# io-board-a-6.net
KiCad netlist of a schematic drawn in EAGLE
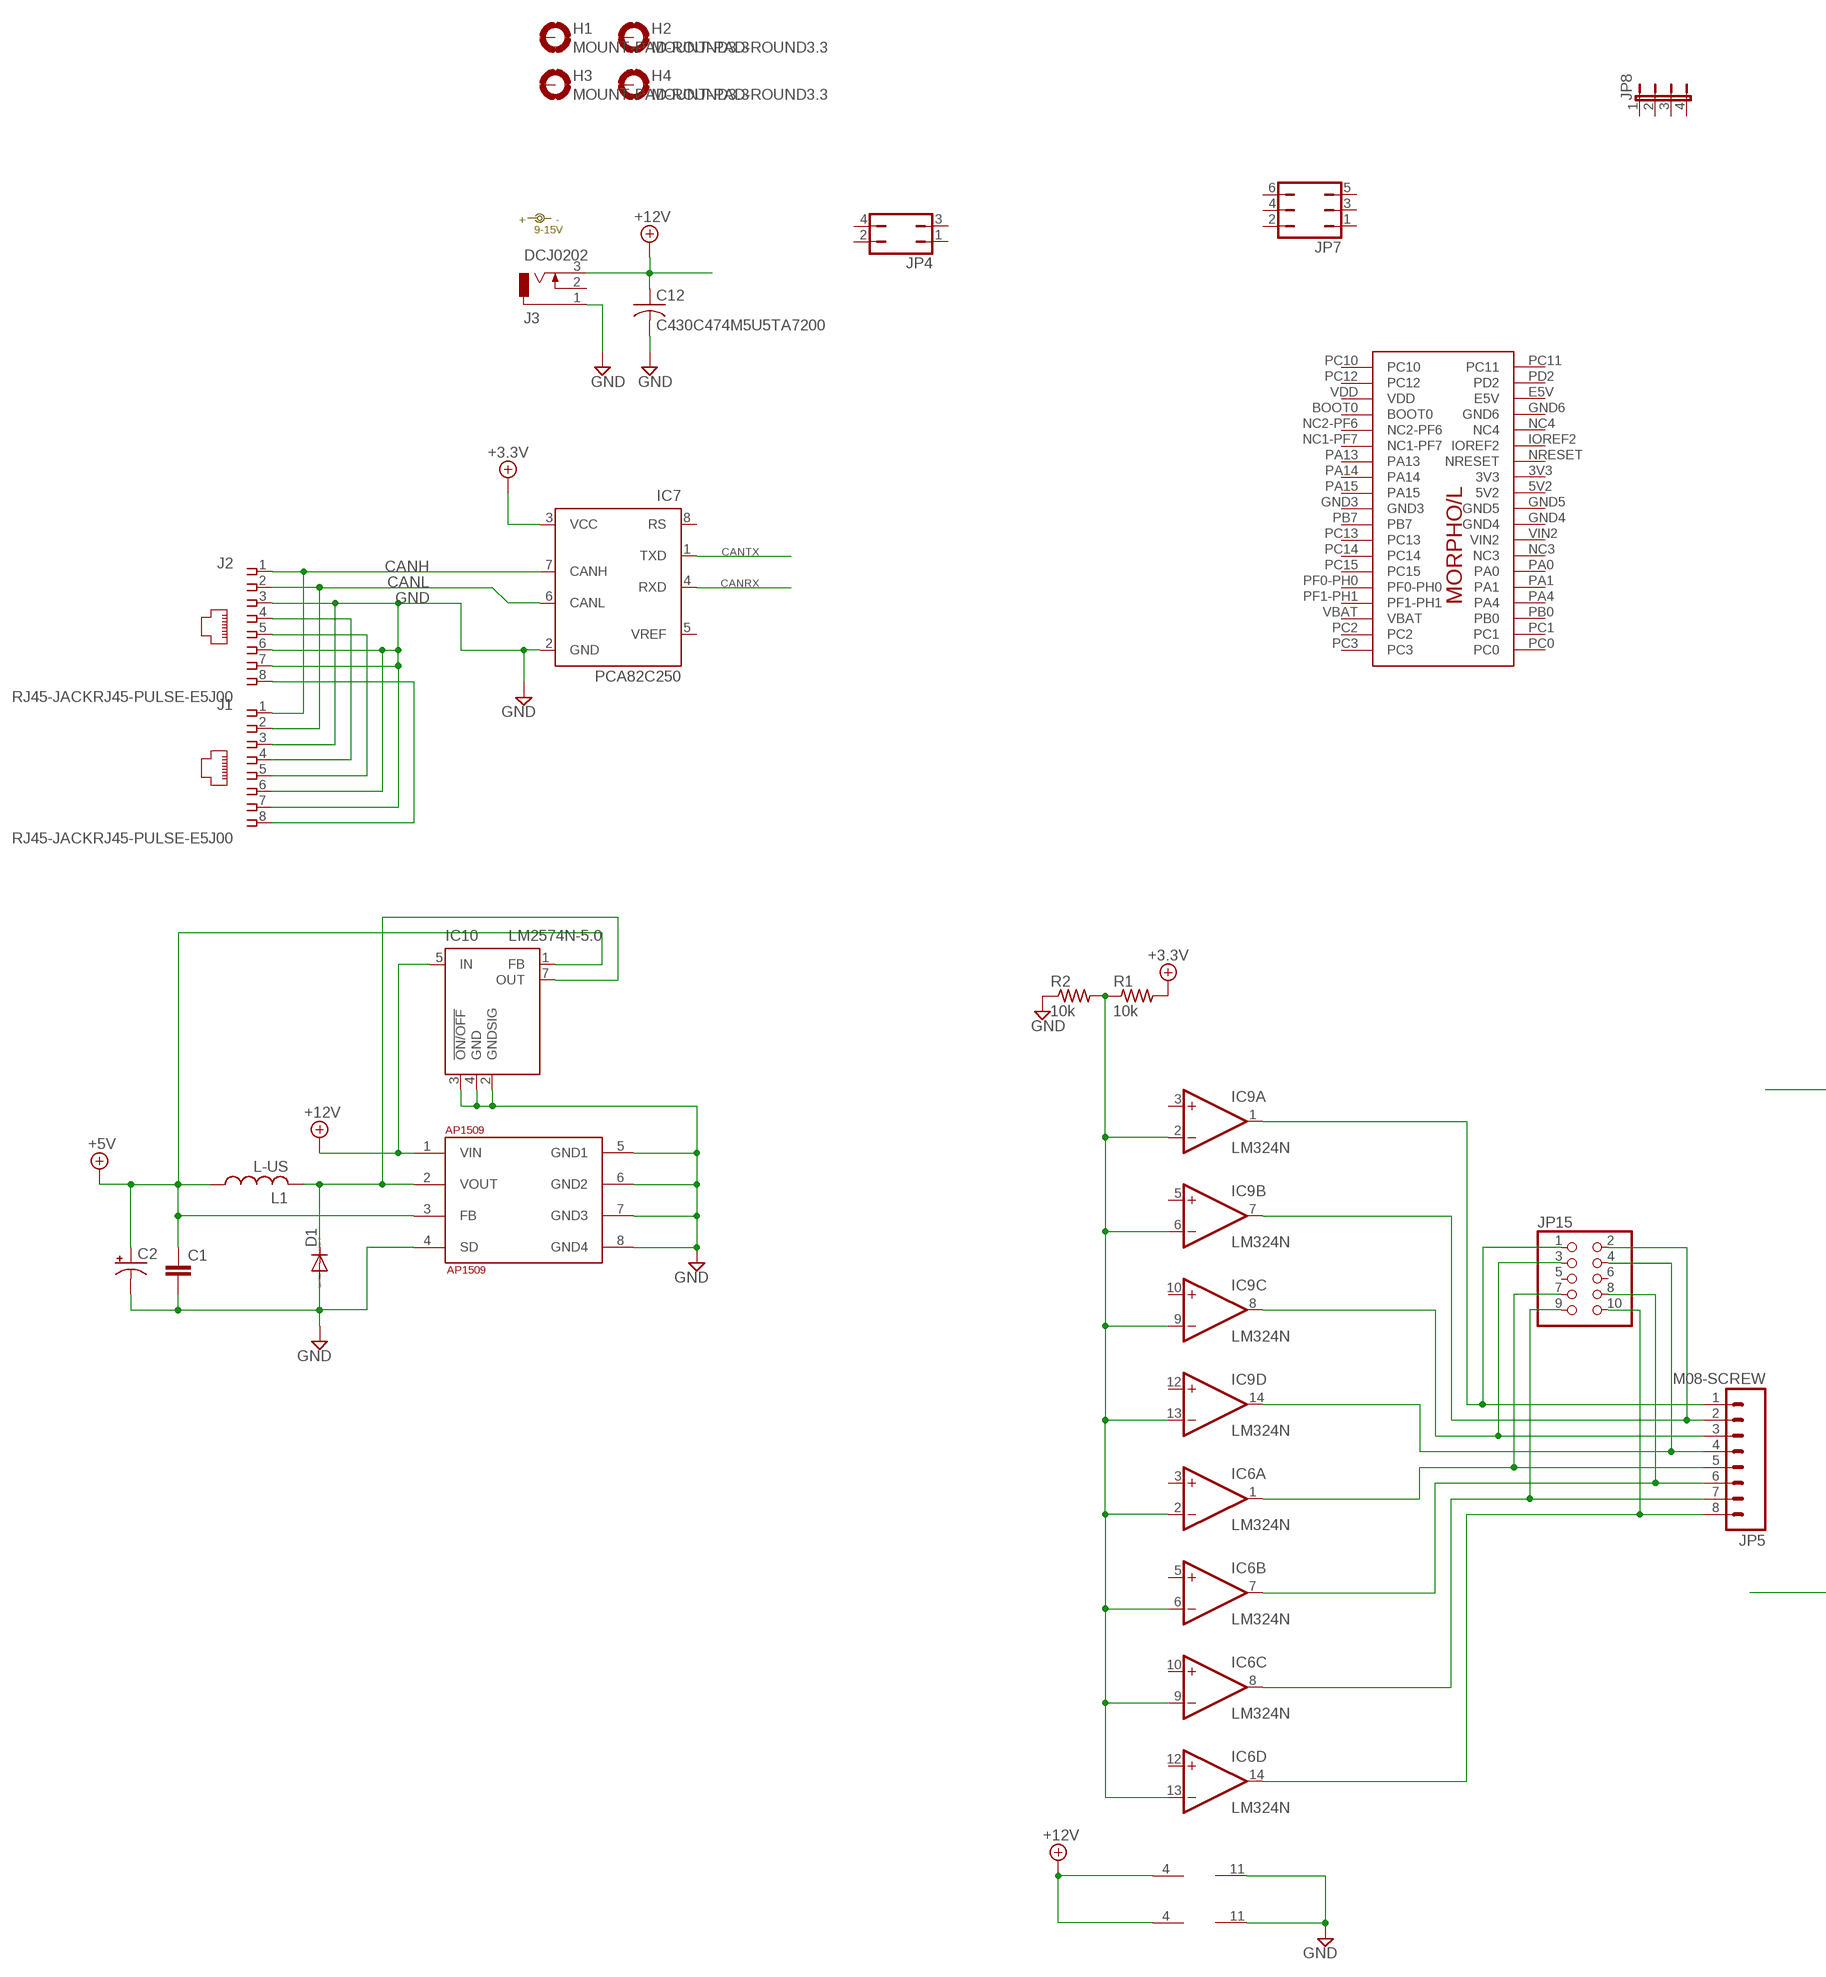
[diagram p0: schematic, sheet 1, part 1 of 2]
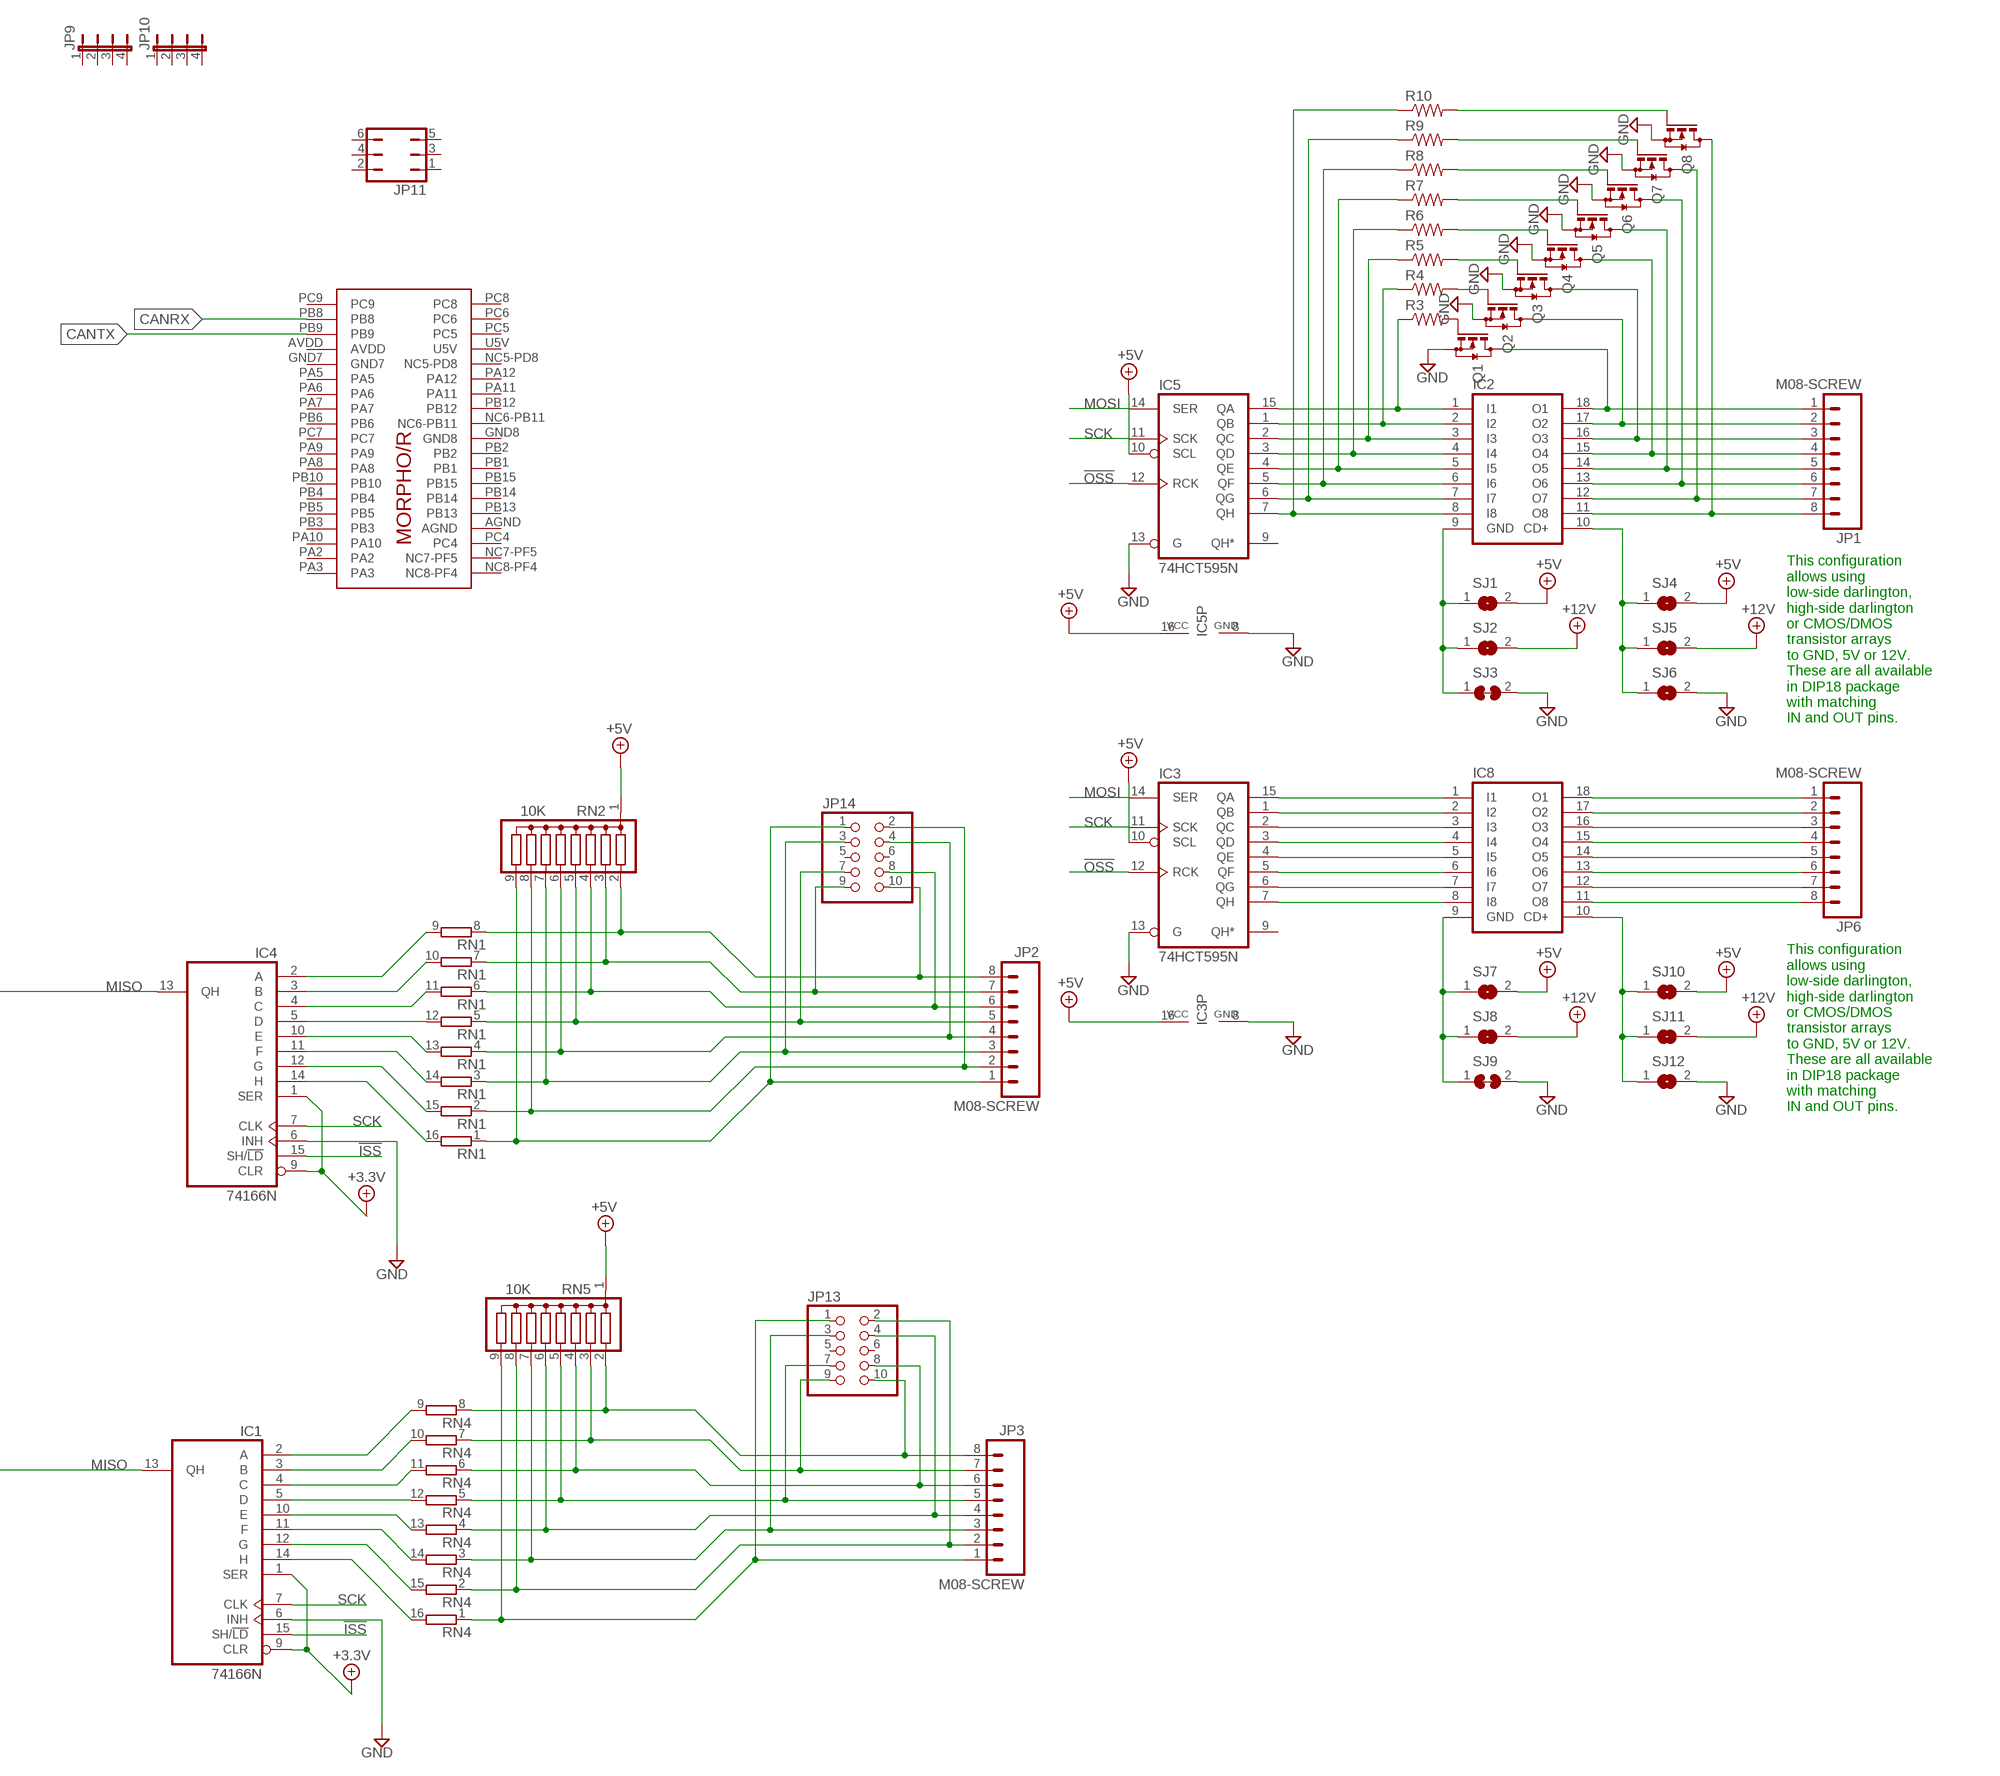
[diagram p1: schematic, sheet 1, part 2 of 2]

(export (version "E")
  (design (tool "Eeschema 10.0.6"))
  (components
    (comp (ref "+12V")
      (value "9-15V")
      (footprint "eagle-import:POWER_USAGE")
      (libsource (lib "eagle-import") (part "DOC-POWER_LABEL"))
    )
    (comp (ref "AP1509")
      (value "AP1509")
      (footprint "eagle-import:SO-08")
      (libsource (lib "eagle-import") (part "AP1509"))
    )
    (comp (ref "C1")
      (value "C-EUC1206")
      (footprint "eagle-import:C1206")
      (libsource (lib "eagle-import") (part "C-EUC1206"))
    )
    (comp (ref "C2")
      (value "CPOL-USE2.5-5")
      (footprint "eagle-import:E2,5-5")
      (libsource (lib "eagle-import") (part "CPOL-USE2.5-5"))
    )
    (comp (ref "C12")
      (value "C430C474M5U5TA7200")
      (footprint "eagle-import:C075-032X103")
      (libsource (lib "eagle-import") (part "C-US075-032X103"))
    )
    (comp (ref "D1")
      (value "DIODE-DO41-7.6")
      (footprint "eagle-import:DO41-7.6")
      (libsource (lib "eagle-import") (part "DIODE-DO41-7.6"))
    )
    (comp (ref "H1")
      (value "MOUNT-PAD-ROUND3.3")
      (footprint "eagle-import:3,3-PAD")
      (libsource (lib "eagle-import") (part "MOUNT-PAD-ROUND3.3"))
    )
    (comp (ref "H2")
      (value "MOUNT-PAD-ROUND3.3")
      (footprint "eagle-import:3,3-PAD")
      (libsource (lib "eagle-import") (part "MOUNT-PAD-ROUND3.3"))
    )
    (comp (ref "H3")
      (value "MOUNT-PAD-ROUND3.3")
      (footprint "eagle-import:3,3-PAD")
      (libsource (lib "eagle-import") (part "MOUNT-PAD-ROUND3.3"))
    )
    (comp (ref "H4")
      (value "MOUNT-PAD-ROUND3.3")
      (footprint "eagle-import:3,3-PAD")
      (libsource (lib "eagle-import") (part "MOUNT-PAD-ROUND3.3"))
    )
    (comp (ref "IC1")
      (value "74166N")
      (footprint "eagle-import:DIL16")
      (libsource (lib "eagle-import") (part "74166N"))
    )
    (comp (ref "IC2")
      (value "ULN2803A")
      (footprint "eagle-import:DIL18-THIN")
      (libsource (lib "eagle-import") (part "ULN2803A"))
    )
    (comp (ref "IC3")
      (value "74HCT595N")
      (footprint "eagle-import:DIL16")
      (libsource (lib "eagle-import") (part "74595NHCT"))
    )
    (comp (ref "IC4")
      (value "74166N")
      (footprint "eagle-import:DIL16")
      (libsource (lib "eagle-import") (part "74166N"))
    )
    (comp (ref "IC5")
      (value "74HCT595N")
      (footprint "eagle-import:DIL16")
      (libsource (lib "eagle-import") (part "74595NHCT"))
    )
    (comp (ref "IC6")
      (value "LM324N")
      (footprint "eagle-import:DIL14")
      (libsource (lib "eagle-import") (part "LM324N"))
    )
    (comp (ref "IC7")
      (value "PCA82C250")
      (footprint "eagle-import:DIL08")
      (libsource (lib "eagle-import") (part "PCA82C250"))
    )
    (comp (ref "IC8")
      (value "ULN2803A")
      (footprint "eagle-import:DIL18-THIN")
      (libsource (lib "eagle-import") (part "ULN2803A"))
    )
    (comp (ref "IC9")
      (value "LM324N")
      (footprint "eagle-import:DIL14")
      (libsource (lib "eagle-import") (part "LM324N"))
    )
    (comp (ref "IC10")
      (value "LM2574N-5.0")
      (footprint "eagle-import:DIL08")
      (libsource (lib "eagle-import") (part "LM2574?-N5.0"))
    )
    (comp (ref "J1")
      (value "RJ45-JACKRJ45-PULSE-E5J00")
      (footprint "eagle-import:RJ45-PULSE-E5J88")
      (libsource (lib "eagle-import") (part "RJ45-JACKRJ45-PULSE-E5J00"))
    )
    (comp (ref "J2")
      (value "RJ45-JACKRJ45-PULSE-E5J00")
      (footprint "eagle-import:RJ45-PULSE-E5J88")
      (libsource (lib "eagle-import") (part "RJ45-JACKRJ45-PULSE-E5J00"))
    )
    (comp (ref "J3")
      (value "DCJ0202")
      (footprint "eagle-import:DCJ0202")
      (libsource (lib "eagle-import") (part "DCJ0202"))
    )
    (comp (ref "JP1")
      (value "M08-SCREW")
      (footprint "eagle-import:1X08_TERMINAL")
      (libsource (lib "eagle-import") (part "M08-SCREW"))
    )
    (comp (ref "JP2")
      (value "M08-SCREW")
      (footprint "eagle-import:1X08_TERMINAL")
      (libsource (lib "eagle-import") (part "M08-SCREW"))
    )
    (comp (ref "JP3")
      (value "M08-SCREW")
      (footprint "eagle-import:1X08_TERMINAL")
      (libsource (lib "eagle-import") (part "M08-SCREW"))
    )
    (comp (ref "JP4")
      (value "JP2Q")
      (footprint "eagle-import:JP2Q")
      (libsource (lib "eagle-import") (part "JP2Q"))
    )
    (comp (ref "JP5")
      (value "M08-SCREW")
      (footprint "eagle-import:1X08_TERMINAL")
      (libsource (lib "eagle-import") (part "M08-SCREW"))
    )
    (comp (ref "JP6")
      (value "M08-SCREW")
      (footprint "eagle-import:1X08_TERMINAL")
      (libsource (lib "eagle-import") (part "M08-SCREW"))
    )
    (comp (ref "JP7")
      (value "JP3Q")
      (footprint "eagle-import:JP3Q")
      (libsource (lib "eagle-import") (part "JP3Q"))
    )
    (comp (ref "JP8")
      (value "JP4-FLAT")
      (footprint "eagle-import:JP4F")
      (libsource (lib "eagle-import") (part "JP4-FLAT"))
    )
    (comp (ref "JP9")
      (value "JP4-FLAT")
      (footprint "eagle-import:JP4F")
      (libsource (lib "eagle-import") (part "JP4-FLAT"))
    )
    (comp (ref "JP10")
      (value "JP4-FLAT")
      (footprint "eagle-import:JP4F")
      (libsource (lib "eagle-import") (part "JP4-FLAT"))
    )
    (comp (ref "JP11")
      (value "JP3Q")
      (footprint "eagle-import:JP3Q")
      (libsource (lib "eagle-import") (part "JP3Q"))
    )
    (comp (ref "JP13")
      (value "PINHD-2X5CN")
      (footprint "eagle-import:CON10M")
      (libsource (lib "eagle-import") (part "PINHD-2X5CN"))
    )
    (comp (ref "JP14")
      (value "PINHD-2X5CN")
      (footprint "eagle-import:CON10M")
      (libsource (lib "eagle-import") (part "PINHD-2X5CN"))
    )
    (comp (ref "JP15")
      (value "PINHD-2X5CN")
      (footprint "eagle-import:CON10M")
      (libsource (lib "eagle-import") (part "PINHD-2X5CN"))
    )
    (comp (ref "L1")
      (value "L-US")
      (footprint "eagle-import:L5-8,5")
      (libsource (lib "eagle-import") (part "L-US"))
    )
    (comp (ref "Q1")
      (value "BSS123")
      (footprint "eagle-import:SOT23")
      (libsource (lib "eagle-import") (part "BSS123"))
    )
    (comp (ref "Q2")
      (value "BSS123")
      (footprint "eagle-import:SOT23")
      (libsource (lib "eagle-import") (part "BSS123"))
    )
    (comp (ref "Q3")
      (value "BSS123")
      (footprint "eagle-import:SOT23")
      (libsource (lib "eagle-import") (part "BSS123"))
    )
    (comp (ref "Q4")
      (value "BSS123")
      (footprint "eagle-import:SOT23")
      (libsource (lib "eagle-import") (part "BSS123"))
    )
    (comp (ref "Q5")
      (value "BSS123")
      (footprint "eagle-import:SOT23")
      (libsource (lib "eagle-import") (part "BSS123"))
    )
    (comp (ref "Q6")
      (value "BSS123")
      (footprint "eagle-import:SOT23")
      (libsource (lib "eagle-import") (part "BSS123"))
    )
    (comp (ref "Q7")
      (value "BSS123")
      (footprint "eagle-import:SOT23")
      (libsource (lib "eagle-import") (part "BSS123"))
    )
    (comp (ref "Q8")
      (value "BSS123")
      (footprint "eagle-import:SOT23")
      (libsource (lib "eagle-import") (part "BSS123"))
    )
    (comp (ref "R1")
      (value "10k")
      (footprint "eagle-import:R1206")
      (libsource (lib "eagle-import") (part "R-US_R1206"))
    )
    (comp (ref "R2")
      (value "10k")
      (footprint "eagle-import:R1206")
      (libsource (lib "eagle-import") (part "R-US_R1206"))
    )
    (comp (ref "R3")
      (value "R-US_R0603")
      (footprint "eagle-import:R0603")
      (libsource (lib "eagle-import") (part "R-US_R0603"))
    )
    (comp (ref "R4")
      (value "R-US_R0603")
      (footprint "eagle-import:R0603")
      (libsource (lib "eagle-import") (part "R-US_R0603"))
    )
    (comp (ref "R5")
      (value "R-US_R0603")
      (footprint "eagle-import:R0603")
      (libsource (lib "eagle-import") (part "R-US_R0603"))
    )
    (comp (ref "R6")
      (value "R-US_R0603")
      (footprint "eagle-import:R0603")
      (libsource (lib "eagle-import") (part "R-US_R0603"))
    )
    (comp (ref "R7")
      (value "R-US_R0603")
      (footprint "eagle-import:R0603")
      (libsource (lib "eagle-import") (part "R-US_R0603"))
    )
    (comp (ref "R8")
      (value "R-US_R0603")
      (footprint "eagle-import:R0603")
      (libsource (lib "eagle-import") (part "R-US_R0603"))
    )
    (comp (ref "R9")
      (value "R-US_R0603")
      (footprint "eagle-import:R0603")
      (libsource (lib "eagle-import") (part "R-US_R0603"))
    )
    (comp (ref "R10")
      (value "R-US_R0603")
      (footprint "eagle-import:R0603")
      (libsource (lib "eagle-import") (part "R-US_R0603"))
    )
    (comp (ref "RN1")
      (value "8R-P")
      (footprint "eagle-import:DIL16")
      (libsource (lib "eagle-import") (part "8R-P"))
    )
    (comp (ref "RN2")
      (value "10K")
      (footprint "eagle-import:SIL9")
      (libsource (lib "eagle-import") (part "G08R"))
    )
    (comp (ref "RN4")
      (value "8R-P")
      (footprint "eagle-import:DIL16")
      (libsource (lib "eagle-import") (part "8R-P"))
    )
    (comp (ref "RN5")
      (value "10K")
      (footprint "eagle-import:SIL9")
      (libsource (lib "eagle-import") (part "G08R"))
    )
    (comp (ref "SJ1")
      (value "SJ")
      (footprint "eagle-import:SJ-RND")
      (libsource (lib "eagle-import") (part "SJ"))
    )
    (comp (ref "SJ2")
      (value "SJ")
      (footprint "eagle-import:SJ-RND")
      (libsource (lib "eagle-import") (part "SJ"))
    )
    (comp (ref "SJ3")
      (value "SJ-C")
      (footprint "eagle-import:SJW-C")
      (libsource (lib "eagle-import") (part "SJ-C"))
    )
    (comp (ref "SJ4")
      (value "SJ")
      (footprint "eagle-import:SJ-RND")
      (libsource (lib "eagle-import") (part "SJ"))
    )
    (comp (ref "SJ5")
      (value "SJ")
      (footprint "eagle-import:SJ-RND")
      (libsource (lib "eagle-import") (part "SJ"))
    )
    (comp (ref "SJ6")
      (value "SJ")
      (footprint "eagle-import:SJ-RND")
      (libsource (lib "eagle-import") (part "SJ"))
    )
    (comp (ref "SJ7")
      (value "SJ")
      (footprint "eagle-import:SJ-RND")
      (libsource (lib "eagle-import") (part "SJ"))
    )
    (comp (ref "SJ8")
      (value "SJ")
      (footprint "eagle-import:SJ-RND")
      (libsource (lib "eagle-import") (part "SJ"))
    )
    (comp (ref "SJ9")
      (value "SJ-C")
      (footprint "eagle-import:SJW-C")
      (libsource (lib "eagle-import") (part "SJ-C"))
    )
    (comp (ref "SJ10")
      (value "SJ")
      (footprint "eagle-import:SJ-RND")
      (libsource (lib "eagle-import") (part "SJ"))
    )
    (comp (ref "SJ11")
      (value "SJ")
      (footprint "eagle-import:SJ-RND")
      (libsource (lib "eagle-import") (part "SJ"))
    )
    (comp (ref "SJ12")
      (value "SJ")
      (footprint "eagle-import:SJ-RND")
      (libsource (lib "eagle-import") (part "SJ"))
    )
    (comp (ref "U$1")
      (value "NUCLEO_64_GENERIC")
      (footprint "eagle-import:NUCLEO_BRD_BASE64")
      (libsource (lib "eagle-import") (part "NUCLEO_64_GENERIC"))
    )
  )
  (nets
    (net (code "1") (name "+3.3V") (class "Default")
      (node (ref "IC1") (pin "1") (pinfunction "SER_1") (pintype "input"))
      (node (ref "IC1") (pin "9") (pinfunction "CLR_9") (pintype "input"))
      (node (ref "IC4") (pin "1") (pinfunction "SER_1") (pintype "input"))
      (node (ref "IC4") (pin "9") (pinfunction "CLR_9") (pintype "input"))
      (node (ref "IC7") (pin "3") (pinfunction "VCC_3") (pintype "power_in"))
      (node (ref "R1") (pin "2") (pinfunction "2_2") (pintype "passive"))
    )
    (net (code "2") (name "+5V") (class "Default")
      (node (ref "AP1509") (pin "3") (pinfunction "FB_3") (pintype "bidirectional"))
      (node (ref "C1") (pin "1") (pinfunction "1_1") (pintype "passive"))
      (node (ref "C2") (pin "+") (pinfunction "+_+") (pintype "passive"))
      (node (ref "IC10") (pin "1") (pinfunction "FB_1") (pintype "input"))
      (node (ref "IC3") (pin "10") (pinfunction "SCL_10") (pintype "input"))
      (node (ref "IC3") (pin "16") (pinfunction "VCC_16") (pintype "power_in"))
      (node (ref "IC5") (pin "10") (pinfunction "SCL_10") (pintype "input"))
      (node (ref "IC5") (pin "16") (pinfunction "VCC_16") (pintype "power_in"))
      (node (ref "L1") (pin "1") (pinfunction "1_1") (pintype "passive"))
      (node (ref "RN2") (pin "1") (pinfunction "1_1") (pintype "passive"))
      (node (ref "RN5") (pin "1") (pinfunction "1_1") (pintype "passive"))
      (node (ref "SJ1") (pin "2") (pinfunction "2_2") (pintype "passive"))
      (node (ref "SJ10") (pin "2") (pinfunction "2_2") (pintype "passive"))
      (node (ref "SJ4") (pin "2") (pinfunction "2_2") (pintype "passive"))
      (node (ref "SJ7") (pin "2") (pinfunction "2_2") (pintype "passive"))
    )
    (net (code "3") (name "+12V") (class "Default")
      (node (ref "AP1509") (pin "1") (pinfunction "VIN_1") (pintype "bidirectional"))
      (node (ref "C12") (pin "1") (pinfunction "1_1") (pintype "passive"))
      (node (ref "IC10") (pin "5") (pinfunction "IN_5") (pintype "input"))
      (node (ref "IC6") (pin "4") (pinfunction "V+_4") (pintype "power_in"))
      (node (ref "IC9") (pin "4") (pinfunction "V+_4") (pintype "power_in"))
      (node (ref "J3") (pin "3") (pinfunction "3_3") (pintype "passive"))
      (node (ref "SJ11") (pin "2") (pinfunction "2_2") (pintype "passive"))
      (node (ref "SJ2") (pin "2") (pinfunction "2_2") (pintype "passive"))
      (node (ref "SJ5") (pin "2") (pinfunction "2_2") (pintype "passive"))
      (node (ref "SJ8") (pin "2") (pinfunction "2_2") (pintype "passive"))
    )
    (net (code "4") (name "/3V3") (class "Default")
      (node (ref "U$1") (pin "3V3") (pinfunction "3V3_3V3") (pintype "power_in"))
    )
    (net (code "5") (name "/5V2") (class "Default")
      (node (ref "U$1") (pin "5V2") (pinfunction "5V2_5V2") (pintype "power_in"))
    )
    (net (code "6") (name "/AGND") (class "Default")
      (node (ref "U$1") (pin "AGND") (pinfunction "AGND_AGND") (pintype "power_in"))
    )
    (net (code "7") (name "/AVDD") (class "Default")
      (node (ref "U$1") (pin "AVDD") (pinfunction "AVDD_AVDD") (pintype "power_in"))
    )
    (net (code "8") (name "/CANH") (class "Default")
      (node (ref "IC7") (pin "7") (pinfunction "CANH_7") (pintype "bidirectional"))
      (node (ref "J1") (pin "1") (pinfunction "1_1") (pintype "passive"))
      (node (ref "J2") (pin "1") (pinfunction "1_1") (pintype "passive"))
    )
    (net (code "9") (name "/CANL") (class "Default")
      (node (ref "IC7") (pin "6") (pinfunction "CANL_6") (pintype "bidirectional"))
      (node (ref "J1") (pin "2") (pinfunction "2_2") (pintype "passive"))
      (node (ref "J2") (pin "2") (pinfunction "2_2") (pintype "passive"))
    )
    (net (code "10") (name "/E5V") (class "Default")
      (node (ref "U$1") (pin "E5V") (pinfunction "E5V_E5V") (pintype "power_in"))
    )
    (net (code "11") (name "/GND3") (class "Default")
      (node (ref "U$1") (pin "GND3") (pinfunction "GND3_GND3") (pintype "power_in"))
    )
    (net (code "12") (name "/GND4") (class "Default")
      (node (ref "U$1") (pin "GND4") (pinfunction "GND4_GND4") (pintype "power_in"))
    )
    (net (code "13") (name "/GND5") (class "Default")
      (node (ref "U$1") (pin "GND5") (pinfunction "GND5_GND5") (pintype "power_in"))
    )
    (net (code "14") (name "/GND6") (class "Default")
      (node (ref "U$1") (pin "GND6") (pinfunction "GND6_GND6") (pintype "power_in"))
    )
    (net (code "15") (name "/GND7") (class "Default")
      (node (ref "U$1") (pin "GND7") (pinfunction "GND7_GND7") (pintype "power_in"))
    )
    (net (code "16") (name "/GND8") (class "Default")
      (node (ref "U$1") (pin "GND8") (pinfunction "GND8_GND8") (pintype "power_in"))
    )
    (net (code "17") (name "/MISO") (class "Default")
      (node (ref "IC1") (pin "13") (pinfunction "QH_13") (pintype "output"))
      (node (ref "IC4") (pin "13") (pinfunction "QH_13") (pintype "output"))
    )
    (net (code "18") (name "/MOSI") (class "Default")
      (node (ref "IC3") (pin "14") (pinfunction "SER_14") (pintype "input"))
      (node (ref "IC5") (pin "14") (pinfunction "SER_14") (pintype "input"))
    )
    (net (code "19") (name "/SCK") (class "Default")
      (node (ref "IC1") (pin "7") (pinfunction "CLK_7") (pintype "input"))
      (node (ref "IC3") (pin "11") (pinfunction "SCK_11") (pintype "input"))
      (node (ref "IC4") (pin "7") (pinfunction "CLK_7") (pintype "input"))
      (node (ref "IC5") (pin "11") (pinfunction "SCK_11") (pintype "input"))
    )
    (net (code "20") (name "/U5V") (class "Default")
      (node (ref "U$1") (pin "U5V") (pinfunction "U5V_U5V") (pintype "power_in"))
    )
    (net (code "21") (name "/VBAT") (class "Default")
      (node (ref "U$1") (pin "VBAT") (pinfunction "VBAT_VBAT") (pintype "power_in"))
    )
    (net (code "22") (name "/VDD") (class "Default")
      (node (ref "U$1") (pin "VDD") (pinfunction "VDD_VDD") (pintype "power_in"))
    )
    (net (code "23") (name "/VIN2") (class "Default")
      (node (ref "U$1") (pin "VIN2") (pinfunction "VIN2_VIN2") (pintype "power_in"))
    )
    (net (code "24") (name "/~{ISS}") (class "Default")
      (node (ref "IC1") (pin "15") (pinfunction "SH/~{LD}_15") (pintype "input"))
      (node (ref "IC4") (pin "15") (pinfunction "SH/~{LD}_15") (pintype "input"))
    )
    (net (code "25") (name "/~{OSS}") (class "Default")
      (node (ref "IC3") (pin "12") (pinfunction "RCK_12") (pintype "input"))
      (node (ref "IC5") (pin "12") (pinfunction "RCK_12") (pintype "input"))
    )
    (net (code "26") (name "CANRX") (class "Default")
      (node (ref "IC7") (pin "4") (pinfunction "RXD_4") (pintype "output"))
      (node (ref "U$1") (pin "PB8") (pinfunction "PB8_PB8") (pintype "bidirectional"))
    )
    (net (code "27") (name "CANTX") (class "Default")
      (node (ref "IC7") (pin "1") (pinfunction "TXD_1") (pintype "input"))
      (node (ref "U$1") (pin "PB9") (pinfunction "PB9_PB9") (pintype "bidirectional"))
    )
    (net (code "28") (name "GND") (class "Default")
      (node (ref "AP1509") (pin "4") (pinfunction "SD_4") (pintype "bidirectional"))
      (node (ref "AP1509") (pin "5") (pinfunction "GND1_5") (pintype "power_in"))
      (node (ref "AP1509") (pin "6") (pinfunction "GND2_6") (pintype "power_in"))
      (node (ref "AP1509") (pin "7") (pinfunction "GND3_7") (pintype "power_in"))
      (node (ref "AP1509") (pin "8") (pinfunction "GND4_8") (pintype "power_in"))
      (node (ref "C1") (pin "2") (pinfunction "2_2") (pintype "passive"))
      (node (ref "C12") (pin "2") (pinfunction "2_2") (pintype "passive"))
      (node (ref "C2") (pin "-") (pinfunction "-_-") (pintype "passive"))
      (node (ref "D1") (pin "A") (pinfunction "A_A") (pintype "passive"))
      (node (ref "IC1") (pin "6") (pinfunction "INH_6") (pintype "input"))
      (node (ref "IC10") (pin "2") (pinfunction "GNDSIG_2") (pintype "input"))
      (node (ref "IC10") (pin "3") (pinfunction "~{ON/OFF}_3") (pintype "input"))
      (node (ref "IC10") (pin "4") (pinfunction "GND_4") (pintype "power_in"))
      (node (ref "IC3") (pin "13") (pinfunction "G_13") (pintype "input"))
      (node (ref "IC3") (pin "8") (pinfunction "GND_8") (pintype "power_in"))
      (node (ref "IC4") (pin "6") (pinfunction "INH_6") (pintype "input"))
      (node (ref "IC5") (pin "13") (pinfunction "G_13") (pintype "input"))
      (node (ref "IC5") (pin "8") (pinfunction "GND_8") (pintype "power_in"))
      (node (ref "IC6") (pin "11") (pinfunction "V-_11") (pintype "power_in"))
      (node (ref "IC7") (pin "2") (pinfunction "GND_2") (pintype "power_in"))
      (node (ref "IC9") (pin "11") (pinfunction "V-_11") (pintype "power_in"))
      (node (ref "J1") (pin "3") (pinfunction "3_3") (pintype "passive"))
      (node (ref "J1") (pin "6") (pinfunction "6_6") (pintype "passive"))
      (node (ref "J1") (pin "7") (pinfunction "7_7") (pintype "passive"))
      (node (ref "J2") (pin "3") (pinfunction "3_3") (pintype "passive"))
      (node (ref "J2") (pin "6") (pinfunction "6_6") (pintype "passive"))
      (node (ref "J2") (pin "7") (pinfunction "7_7") (pintype "passive"))
      (node (ref "J3") (pin "1") (pinfunction "1_1") (pintype "passive"))
      (node (ref "Q1") (pin "2") (pinfunction "S_2") (pintype "passive"))
      (node (ref "Q2") (pin "2") (pinfunction "S_2") (pintype "passive"))
      (node (ref "Q3") (pin "2") (pinfunction "S_2") (pintype "passive"))
      (node (ref "Q4") (pin "2") (pinfunction "S_2") (pintype "passive"))
      (node (ref "Q5") (pin "2") (pinfunction "S_2") (pintype "passive"))
      (node (ref "Q6") (pin "2") (pinfunction "S_2") (pintype "passive"))
      (node (ref "Q7") (pin "2") (pinfunction "S_2") (pintype "passive"))
      (node (ref "Q8") (pin "2") (pinfunction "S_2") (pintype "passive"))
      (node (ref "R2") (pin "1") (pinfunction "1_1") (pintype "passive"))
      (node (ref "SJ12") (pin "2") (pinfunction "2_2") (pintype "passive"))
      (node (ref "SJ3") (pin "2") (pinfunction "2_2") (pintype "passive"))
      (node (ref "SJ6") (pin "2") (pinfunction "2_2") (pintype "passive"))
      (node (ref "SJ9") (pin "2") (pinfunction "2_2") (pintype "passive"))
    )
    (net (code "29") (name "Net-(AP1509-VOUT)") (class "Default")
      (node (ref "AP1509") (pin "2") (pinfunction "VOUT_2") (pintype "bidirectional"))
      (node (ref "D1") (pin "C") (pinfunction "C_C") (pintype "passive"))
      (node (ref "IC10") (pin "7") (pinfunction "OUT_7") (pintype "passive"))
      (node (ref "L1") (pin "2") (pinfunction "2_2") (pintype "passive"))
    )
    (net (code "30") (name "Net-(IC1A-A)") (class "Default")
      (node (ref "IC1") (pin "2") (pinfunction "A_2") (pintype "input"))
      (node (ref "RN4") (pin "9") (pinfunction "2_9") (pintype "passive"))
    )
    (net (code "31") (name "Net-(IC1A-B)") (class "Default")
      (node (ref "IC1") (pin "3") (pinfunction "B_3") (pintype "input"))
      (node (ref "RN4") (pin "10") (pinfunction "2_10") (pintype "passive"))
    )
    (net (code "32") (name "Net-(IC1A-C)") (class "Default")
      (node (ref "IC1") (pin "4") (pinfunction "C_4") (pintype "input"))
      (node (ref "RN4") (pin "11") (pinfunction "2_11") (pintype "passive"))
    )
    (net (code "33") (name "Net-(IC1A-D)") (class "Default")
      (node (ref "IC1") (pin "5") (pinfunction "D_5") (pintype "input"))
      (node (ref "RN4") (pin "12") (pinfunction "2_12") (pintype "passive"))
    )
    (net (code "34") (name "Net-(IC1A-E)") (class "Default")
      (node (ref "IC1") (pin "10") (pinfunction "E_10") (pintype "input"))
      (node (ref "RN4") (pin "13") (pinfunction "2_13") (pintype "passive"))
    )
    (net (code "35") (name "Net-(IC1A-F)") (class "Default")
      (node (ref "IC1") (pin "11") (pinfunction "F_11") (pintype "input"))
      (node (ref "RN4") (pin "14") (pinfunction "2_14") (pintype "passive"))
    )
    (net (code "36") (name "Net-(IC1A-G)") (class "Default")
      (node (ref "IC1") (pin "12") (pinfunction "G_12") (pintype "input"))
      (node (ref "RN4") (pin "15") (pinfunction "2_15") (pintype "passive"))
    )
    (net (code "37") (name "Net-(IC1A-H)") (class "Default")
      (node (ref "IC1") (pin "14") (pinfunction "H_14") (pintype "input"))
      (node (ref "RN4") (pin "16") (pinfunction "2_16") (pintype "passive"))
    )
    (net (code "38") (name "Net-(IC2-CD+)") (class "Default")
      (node (ref "IC2") (pin "10") (pinfunction "CD+_10") (pintype "passive"))
      (node (ref "SJ4") (pin "1") (pinfunction "1_1") (pintype "passive"))
      (node (ref "SJ5") (pin "1") (pinfunction "1_1") (pintype "passive"))
      (node (ref "SJ6") (pin "1") (pinfunction "1_1") (pintype "passive"))
    )
    (net (code "39") (name "Net-(IC2-GND)") (class "Default")
      (node (ref "IC2") (pin "9") (pinfunction "GND_9") (pintype "power_in"))
      (node (ref "SJ1") (pin "1") (pinfunction "1_1") (pintype "passive"))
      (node (ref "SJ2") (pin "1") (pinfunction "1_1") (pintype "passive"))
      (node (ref "SJ3") (pin "1") (pinfunction "1_1") (pintype "passive"))
    )
    (net (code "40") (name "Net-(IC2-I1)") (class "Default")
      (node (ref "IC2") (pin "1") (pinfunction "I1_1") (pintype "input"))
      (node (ref "IC5") (pin "15") (pinfunction "QA_15") (pintype "tri_state"))
      (node (ref "R3") (pin "1") (pinfunction "1_1") (pintype "passive"))
    )
    (net (code "41") (name "Net-(IC2-I2)") (class "Default")
      (node (ref "IC2") (pin "2") (pinfunction "I2_2") (pintype "input"))
      (node (ref "IC5") (pin "1") (pinfunction "QB_1") (pintype "tri_state"))
      (node (ref "R4") (pin "1") (pinfunction "1_1") (pintype "passive"))
    )
    (net (code "42") (name "Net-(IC2-I3)") (class "Default")
      (node (ref "IC2") (pin "3") (pinfunction "I3_3") (pintype "input"))
      (node (ref "IC5") (pin "2") (pinfunction "QC_2") (pintype "tri_state"))
      (node (ref "R5") (pin "1") (pinfunction "1_1") (pintype "passive"))
    )
    (net (code "43") (name "Net-(IC2-I4)") (class "Default")
      (node (ref "IC2") (pin "4") (pinfunction "I4_4") (pintype "input"))
      (node (ref "IC5") (pin "3") (pinfunction "QD_3") (pintype "tri_state"))
      (node (ref "R6") (pin "1") (pinfunction "1_1") (pintype "passive"))
    )
    (net (code "44") (name "Net-(IC2-I5)") (class "Default")
      (node (ref "IC2") (pin "5") (pinfunction "I5_5") (pintype "input"))
      (node (ref "IC5") (pin "4") (pinfunction "QE_4") (pintype "tri_state"))
      (node (ref "R7") (pin "1") (pinfunction "1_1") (pintype "passive"))
    )
    (net (code "45") (name "Net-(IC2-I6)") (class "Default")
      (node (ref "IC2") (pin "6") (pinfunction "I6_6") (pintype "input"))
      (node (ref "IC5") (pin "5") (pinfunction "QF_5") (pintype "tri_state"))
      (node (ref "R8") (pin "1") (pinfunction "1_1") (pintype "passive"))
    )
    (net (code "46") (name "Net-(IC2-I7)") (class "Default")
      (node (ref "IC2") (pin "7") (pinfunction "I7_7") (pintype "input"))
      (node (ref "IC5") (pin "6") (pinfunction "QG_6") (pintype "tri_state"))
      (node (ref "R9") (pin "1") (pinfunction "1_1") (pintype "passive"))
    )
    (net (code "47") (name "Net-(IC2-I8)") (class "Default")
      (node (ref "IC2") (pin "8") (pinfunction "I8_8") (pintype "input"))
      (node (ref "IC5") (pin "7") (pinfunction "QH_7") (pintype "tri_state"))
      (node (ref "R10") (pin "1") (pinfunction "1_1") (pintype "passive"))
    )
    (net (code "48") (name "Net-(IC2-O1)") (class "Default")
      (node (ref "IC2") (pin "18") (pinfunction "O1_18") (pintype "open_collector"))
      (node (ref "JP1") (pin "1") (pinfunction "1_1") (pintype "passive"))
      (node (ref "Q1") (pin "3") (pinfunction "D_3") (pintype "passive"))
    )
    (net (code "49") (name "Net-(IC2-O2)") (class "Default")
      (node (ref "IC2") (pin "17") (pinfunction "O2_17") (pintype "open_collector"))
      (node (ref "JP1") (pin "2") (pinfunction "2_2") (pintype "passive"))
      (node (ref "Q2") (pin "3") (pinfunction "D_3") (pintype "passive"))
    )
    (net (code "50") (name "Net-(IC2-O3)") (class "Default")
      (node (ref "IC2") (pin "16") (pinfunction "O3_16") (pintype "open_collector"))
      (node (ref "JP1") (pin "3") (pinfunction "3_3") (pintype "passive"))
      (node (ref "Q3") (pin "3") (pinfunction "D_3") (pintype "passive"))
    )
    (net (code "51") (name "Net-(IC2-O4)") (class "Default")
      (node (ref "IC2") (pin "15") (pinfunction "O4_15") (pintype "open_collector"))
      (node (ref "JP1") (pin "4") (pinfunction "4_4") (pintype "passive"))
      (node (ref "Q4") (pin "3") (pinfunction "D_3") (pintype "passive"))
    )
    (net (code "52") (name "Net-(IC2-O5)") (class "Default")
      (node (ref "IC2") (pin "14") (pinfunction "O5_14") (pintype "open_collector"))
      (node (ref "JP1") (pin "5") (pinfunction "5_5") (pintype "passive"))
      (node (ref "Q5") (pin "3") (pinfunction "D_3") (pintype "passive"))
    )
    (net (code "53") (name "Net-(IC2-O6)") (class "Default")
      (node (ref "IC2") (pin "13") (pinfunction "O6_13") (pintype "open_collector"))
      (node (ref "JP1") (pin "6") (pinfunction "6_6") (pintype "passive"))
      (node (ref "Q6") (pin "3") (pinfunction "D_3") (pintype "passive"))
    )
    (net (code "54") (name "Net-(IC2-O7)") (class "Default")
      (node (ref "IC2") (pin "12") (pinfunction "O7_12") (pintype "open_collector"))
      (node (ref "JP1") (pin "7") (pinfunction "7_7") (pintype "passive"))
      (node (ref "Q7") (pin "3") (pinfunction "D_3") (pintype "passive"))
    )
    (net (code "55") (name "Net-(IC2-O8)") (class "Default")
      (node (ref "IC2") (pin "11") (pinfunction "O8_11") (pintype "open_collector"))
      (node (ref "JP1") (pin "8") (pinfunction "8_8") (pintype "passive"))
      (node (ref "Q8") (pin "3") (pinfunction "D_3") (pintype "passive"))
    )
    (net (code "56") (name "Net-(IC3A-QA)") (class "Default")
      (node (ref "IC3") (pin "15") (pinfunction "QA_15") (pintype "tri_state"))
      (node (ref "IC8") (pin "1") (pinfunction "I1_1") (pintype "input"))
    )
    (net (code "57") (name "Net-(IC3A-QB)") (class "Default")
      (node (ref "IC3") (pin "1") (pinfunction "QB_1") (pintype "tri_state"))
      (node (ref "IC8") (pin "2") (pinfunction "I2_2") (pintype "input"))
    )
    (net (code "58") (name "Net-(IC3A-QC)") (class "Default")
      (node (ref "IC3") (pin "2") (pinfunction "QC_2") (pintype "tri_state"))
      (node (ref "IC8") (pin "3") (pinfunction "I3_3") (pintype "input"))
    )
    (net (code "59") (name "Net-(IC3A-QD)") (class "Default")
      (node (ref "IC3") (pin "3") (pinfunction "QD_3") (pintype "tri_state"))
      (node (ref "IC8") (pin "4") (pinfunction "I4_4") (pintype "input"))
    )
    (net (code "60") (name "Net-(IC3A-QE)") (class "Default")
      (node (ref "IC3") (pin "4") (pinfunction "QE_4") (pintype "tri_state"))
      (node (ref "IC8") (pin "5") (pinfunction "I5_5") (pintype "input"))
    )
    (net (code "61") (name "Net-(IC3A-QF)") (class "Default")
      (node (ref "IC3") (pin "5") (pinfunction "QF_5") (pintype "tri_state"))
      (node (ref "IC8") (pin "6") (pinfunction "I6_6") (pintype "input"))
    )
    (net (code "62") (name "Net-(IC3A-QG)") (class "Default")
      (node (ref "IC3") (pin "6") (pinfunction "QG_6") (pintype "tri_state"))
      (node (ref "IC8") (pin "7") (pinfunction "I7_7") (pintype "input"))
    )
    (net (code "63") (name "Net-(IC3A-QH)") (class "Default")
      (node (ref "IC3") (pin "7") (pinfunction "QH_7") (pintype "tri_state"))
      (node (ref "IC8") (pin "8") (pinfunction "I8_8") (pintype "input"))
    )
    (net (code "64") (name "Net-(IC4A-A)") (class "Default")
      (node (ref "IC4") (pin "2") (pinfunction "A_2") (pintype "input"))
      (node (ref "RN1") (pin "9") (pinfunction "2_9") (pintype "passive"))
    )
    (net (code "65") (name "Net-(IC4A-B)") (class "Default")
      (node (ref "IC4") (pin "3") (pinfunction "B_3") (pintype "input"))
      (node (ref "RN1") (pin "10") (pinfunction "2_10") (pintype "passive"))
    )
    (net (code "66") (name "Net-(IC4A-C)") (class "Default")
      (node (ref "IC4") (pin "4") (pinfunction "C_4") (pintype "input"))
      (node (ref "RN1") (pin "11") (pinfunction "2_11") (pintype "passive"))
    )
    (net (code "67") (name "Net-(IC4A-D)") (class "Default")
      (node (ref "IC4") (pin "5") (pinfunction "D_5") (pintype "input"))
      (node (ref "RN1") (pin "12") (pinfunction "2_12") (pintype "passive"))
    )
    (net (code "68") (name "Net-(IC4A-E)") (class "Default")
      (node (ref "IC4") (pin "10") (pinfunction "E_10") (pintype "input"))
      (node (ref "RN1") (pin "13") (pinfunction "2_13") (pintype "passive"))
    )
    (net (code "69") (name "Net-(IC4A-F)") (class "Default")
      (node (ref "IC4") (pin "11") (pinfunction "F_11") (pintype "input"))
      (node (ref "RN1") (pin "14") (pinfunction "2_14") (pintype "passive"))
    )
    (net (code "70") (name "Net-(IC4A-G)") (class "Default")
      (node (ref "IC4") (pin "12") (pinfunction "G_12") (pintype "input"))
      (node (ref "RN1") (pin "15") (pinfunction "2_15") (pintype "passive"))
    )
    (net (code "71") (name "Net-(IC4A-H)") (class "Default")
      (node (ref "IC4") (pin "14") (pinfunction "H_14") (pintype "input"))
      (node (ref "RN1") (pin "16") (pinfunction "2_16") (pintype "passive"))
    )
    (net (code "72") (name "Net-(IC6A--IN)") (class "Default")
      (node (ref "IC6") (pin "13") (pinfunction "-IN_13") (pintype "input"))
      (node (ref "IC6") (pin "2") (pinfunction "-IN_2") (pintype "input"))
      (node (ref "IC6") (pin "6") (pinfunction "-IN_6") (pintype "input"))
      (node (ref "IC6") (pin "9") (pinfunction "-IN_9") (pintype "input"))
      (node (ref "IC9") (pin "13") (pinfunction "-IN_13") (pintype "input"))
      (node (ref "IC9") (pin "2") (pinfunction "-IN_2") (pintype "input"))
      (node (ref "IC9") (pin "6") (pinfunction "-IN_6") (pintype "input"))
      (node (ref "IC9") (pin "9") (pinfunction "-IN_9") (pintype "input"))
      (node (ref "R1") (pin "1") (pinfunction "1_1") (pintype "passive"))
      (node (ref "R2") (pin "2") (pinfunction "2_2") (pintype "passive"))
    )
    (net (code "73") (name "Net-(IC6A-OUT)") (class "Default")
      (node (ref "IC6") (pin "1") (pinfunction "OUT_1") (pintype "output"))
      (node (ref "JP15") (pin "7") (pinfunction "7_7") (pintype "passive"))
      (node (ref "JP5") (pin "5") (pinfunction "5_5") (pintype "passive"))
    )
    (net (code "74") (name "Net-(IC6B-OUT)") (class "Default")
      (node (ref "IC6") (pin "7") (pinfunction "OUT_7") (pintype "output"))
      (node (ref "JP15") (pin "8") (pinfunction "8_8") (pintype "passive"))
      (node (ref "JP5") (pin "6") (pinfunction "6_6") (pintype "passive"))
    )
    (net (code "75") (name "Net-(IC6C-OUT)") (class "Default")
      (node (ref "IC6") (pin "8") (pinfunction "OUT_8") (pintype "output"))
      (node (ref "JP15") (pin "9") (pinfunction "9_9") (pintype "passive"))
      (node (ref "JP5") (pin "7") (pinfunction "7_7") (pintype "passive"))
    )
    (net (code "76") (name "Net-(IC6D-OUT)") (class "Default")
      (node (ref "IC6") (pin "14") (pinfunction "OUT_14") (pintype "output"))
      (node (ref "JP15") (pin "10") (pinfunction "10_10") (pintype "passive"))
      (node (ref "JP5") (pin "8") (pinfunction "8_8") (pintype "passive"))
    )
    (net (code "77") (name "Net-(IC8-CD+)") (class "Default")
      (node (ref "IC8") (pin "10") (pinfunction "CD+_10") (pintype "passive"))
      (node (ref "SJ10") (pin "1") (pinfunction "1_1") (pintype "passive"))
      (node (ref "SJ11") (pin "1") (pinfunction "1_1") (pintype "passive"))
      (node (ref "SJ12") (pin "1") (pinfunction "1_1") (pintype "passive"))
    )
    (net (code "78") (name "Net-(IC8-GND)") (class "Default")
      (node (ref "IC8") (pin "9") (pinfunction "GND_9") (pintype "power_in"))
      (node (ref "SJ7") (pin "1") (pinfunction "1_1") (pintype "passive"))
      (node (ref "SJ8") (pin "1") (pinfunction "1_1") (pintype "passive"))
      (node (ref "SJ9") (pin "1") (pinfunction "1_1") (pintype "passive"))
    )
    (net (code "79") (name "Net-(IC8-O1)") (class "Default")
      (node (ref "IC8") (pin "18") (pinfunction "O1_18") (pintype "open_collector"))
      (node (ref "JP6") (pin "1") (pinfunction "1_1") (pintype "passive"))
    )
    (net (code "80") (name "Net-(IC8-O2)") (class "Default")
      (node (ref "IC8") (pin "17") (pinfunction "O2_17") (pintype "open_collector"))
      (node (ref "JP6") (pin "2") (pinfunction "2_2") (pintype "passive"))
    )
    (net (code "81") (name "Net-(IC8-O3)") (class "Default")
      (node (ref "IC8") (pin "16") (pinfunction "O3_16") (pintype "open_collector"))
      (node (ref "JP6") (pin "3") (pinfunction "3_3") (pintype "passive"))
    )
    (net (code "82") (name "Net-(IC8-O4)") (class "Default")
      (node (ref "IC8") (pin "15") (pinfunction "O4_15") (pintype "open_collector"))
      (node (ref "JP6") (pin "4") (pinfunction "4_4") (pintype "passive"))
    )
    (net (code "83") (name "Net-(IC8-O5)") (class "Default")
      (node (ref "IC8") (pin "14") (pinfunction "O5_14") (pintype "open_collector"))
      (node (ref "JP6") (pin "5") (pinfunction "5_5") (pintype "passive"))
    )
    (net (code "84") (name "Net-(IC8-O6)") (class "Default")
      (node (ref "IC8") (pin "13") (pinfunction "O6_13") (pintype "open_collector"))
      (node (ref "JP6") (pin "6") (pinfunction "6_6") (pintype "passive"))
    )
    (net (code "85") (name "Net-(IC8-O7)") (class "Default")
      (node (ref "IC8") (pin "12") (pinfunction "O7_12") (pintype "open_collector"))
      (node (ref "JP6") (pin "7") (pinfunction "7_7") (pintype "passive"))
    )
    (net (code "86") (name "Net-(IC8-O8)") (class "Default")
      (node (ref "IC8") (pin "11") (pinfunction "O8_11") (pintype "open_collector"))
      (node (ref "JP6") (pin "8") (pinfunction "8_8") (pintype "passive"))
    )
    (net (code "87") (name "Net-(IC9A-OUT)") (class "Default")
      (node (ref "IC9") (pin "1") (pinfunction "OUT_1") (pintype "output"))
      (node (ref "JP15") (pin "1") (pinfunction "1_1") (pintype "passive"))
      (node (ref "JP5") (pin "1") (pinfunction "1_1") (pintype "passive"))
    )
    (net (code "88") (name "Net-(IC9B-OUT)") (class "Default")
      (node (ref "IC9") (pin "7") (pinfunction "OUT_7") (pintype "output"))
      (node (ref "JP15") (pin "2") (pinfunction "2_2") (pintype "passive"))
      (node (ref "JP5") (pin "2") (pinfunction "2_2") (pintype "passive"))
    )
    (net (code "89") (name "Net-(IC9C-OUT)") (class "Default")
      (node (ref "IC9") (pin "8") (pinfunction "OUT_8") (pintype "output"))
      (node (ref "JP15") (pin "3") (pinfunction "3_3") (pintype "passive"))
      (node (ref "JP5") (pin "3") (pinfunction "3_3") (pintype "passive"))
    )
    (net (code "90") (name "Net-(IC9D-OUT)") (class "Default")
      (node (ref "IC9") (pin "14") (pinfunction "OUT_14") (pintype "output"))
      (node (ref "JP15") (pin "4") (pinfunction "4_4") (pintype "passive"))
      (node (ref "JP5") (pin "4") (pinfunction "4_4") (pintype "passive"))
    )
    (net (code "91") (name "Net-(J1-Pad4)") (class "Default")
      (node (ref "J1") (pin "4") (pinfunction "4_4") (pintype "passive"))
      (node (ref "J2") (pin "4") (pinfunction "4_4") (pintype "passive"))
    )
    (net (code "92") (name "Net-(J1-Pad5)") (class "Default")
      (node (ref "J1") (pin "5") (pinfunction "5_5") (pintype "passive"))
      (node (ref "J2") (pin "5") (pinfunction "5_5") (pintype "passive"))
    )
    (net (code "93") (name "Net-(J1-Pad8)") (class "Default")
      (node (ref "J1") (pin "8") (pinfunction "8_8") (pintype "passive"))
      (node (ref "J2") (pin "8") (pinfunction "8_8") (pintype "passive"))
    )
    (net (code "94") (name "Net-(JP13-Pad1)") (class "Default")
      (node (ref "JP13") (pin "1") (pinfunction "1_1") (pintype "passive"))
      (node (ref "JP3") (pin "1") (pinfunction "1_1") (pintype "passive"))
      (node (ref "RN4") (pin "1") (pinfunction "1_1") (pintype "passive"))
      (node (ref "RN5") (pin "9") (pinfunction "9_9") (pintype "passive"))
    )
    (net (code "95") (name "Net-(JP14-Pad1)") (class "Default")
      (node (ref "JP14") (pin "1") (pinfunction "1_1") (pintype "passive"))
      (node (ref "JP2") (pin "1") (pinfunction "1_1") (pintype "passive"))
      (node (ref "RN1") (pin "1") (pinfunction "1_1") (pintype "passive"))
      (node (ref "RN2") (pin "9") (pinfunction "9_9") (pintype "passive"))
    )
    (net (code "96") (name "Net-(Q1-G)") (class "Default")
      (node (ref "Q1") (pin "1") (pinfunction "G_1") (pintype "passive"))
      (node (ref "R3") (pin "2") (pinfunction "2_2") (pintype "passive"))
    )
    (net (code "97") (name "Net-(Q2-G)") (class "Default")
      (node (ref "Q2") (pin "1") (pinfunction "G_1") (pintype "passive"))
      (node (ref "R4") (pin "2") (pinfunction "2_2") (pintype "passive"))
    )
    (net (code "98") (name "Net-(Q3-G)") (class "Default")
      (node (ref "Q3") (pin "1") (pinfunction "G_1") (pintype "passive"))
      (node (ref "R5") (pin "2") (pinfunction "2_2") (pintype "passive"))
    )
    (net (code "99") (name "Net-(Q4-G)") (class "Default")
      (node (ref "Q4") (pin "1") (pinfunction "G_1") (pintype "passive"))
      (node (ref "R6") (pin "2") (pinfunction "2_2") (pintype "passive"))
    )
    (net (code "100") (name "Net-(Q5-G)") (class "Default")
      (node (ref "Q5") (pin "1") (pinfunction "G_1") (pintype "passive"))
      (node (ref "R7") (pin "2") (pinfunction "2_2") (pintype "passive"))
    )
    (net (code "101") (name "Net-(Q6-G)") (class "Default")
      (node (ref "Q6") (pin "1") (pinfunction "G_1") (pintype "passive"))
      (node (ref "R8") (pin "2") (pinfunction "2_2") (pintype "passive"))
    )
    (net (code "102") (name "Net-(Q7-G)") (class "Default")
      (node (ref "Q7") (pin "1") (pinfunction "G_1") (pintype "passive"))
      (node (ref "R9") (pin "2") (pinfunction "2_2") (pintype "passive"))
    )
    (net (code "103") (name "Net-(Q8-G)") (class "Default")
      (node (ref "Q8") (pin "1") (pinfunction "G_1") (pintype "passive"))
      (node (ref "R10") (pin "2") (pinfunction "2_2") (pintype "passive"))
    )
    (net (code "104") (name "Net-(RN1B-1)") (class "Default")
      (node (ref "JP14") (pin "2") (pinfunction "2_2") (pintype "passive"))
      (node (ref "JP2") (pin "2") (pinfunction "2_2") (pintype "passive"))
      (node (ref "RN1") (pin "2") (pinfunction "1_2") (pintype "passive"))
      (node (ref "RN2") (pin "8") (pinfunction "8_8") (pintype "passive"))
    )
    (net (code "105") (name "Net-(RN1C-1)") (class "Default")
      (node (ref "JP14") (pin "3") (pinfunction "3_3") (pintype "passive"))
      (node (ref "JP2") (pin "3") (pinfunction "3_3") (pintype "passive"))
      (node (ref "RN1") (pin "3") (pinfunction "1_3") (pintype "passive"))
      (node (ref "RN2") (pin "7") (pinfunction "7_7") (pintype "passive"))
    )
    (net (code "106") (name "Net-(RN1D-1)") (class "Default")
      (node (ref "JP14") (pin "4") (pinfunction "4_4") (pintype "passive"))
      (node (ref "JP2") (pin "4") (pinfunction "4_4") (pintype "passive"))
      (node (ref "RN1") (pin "4") (pinfunction "1_4") (pintype "passive"))
      (node (ref "RN2") (pin "6") (pinfunction "6_6") (pintype "passive"))
    )
    (net (code "107") (name "Net-(RN1E-1)") (class "Default")
      (node (ref "JP14") (pin "7") (pinfunction "7_7") (pintype "passive"))
      (node (ref "JP2") (pin "5") (pinfunction "5_5") (pintype "passive"))
      (node (ref "RN1") (pin "5") (pinfunction "1_5") (pintype "passive"))
      (node (ref "RN2") (pin "5") (pinfunction "5_5") (pintype "passive"))
    )
    (net (code "108") (name "Net-(RN1F-1)") (class "Default")
      (node (ref "JP14") (pin "8") (pinfunction "8_8") (pintype "passive"))
      (node (ref "JP2") (pin "6") (pinfunction "6_6") (pintype "passive"))
      (node (ref "RN1") (pin "6") (pinfunction "1_6") (pintype "passive"))
      (node (ref "RN2") (pin "4") (pinfunction "4_4") (pintype "passive"))
    )
    (net (code "109") (name "Net-(RN1G-1)") (class "Default")
      (node (ref "JP14") (pin "9") (pinfunction "9_9") (pintype "passive"))
      (node (ref "JP2") (pin "7") (pinfunction "7_7") (pintype "passive"))
      (node (ref "RN1") (pin "7") (pinfunction "1_7") (pintype "passive"))
      (node (ref "RN2") (pin "3") (pinfunction "3_3") (pintype "passive"))
    )
    (net (code "110") (name "Net-(RN1H-1)") (class "Default")
      (node (ref "JP14") (pin "10") (pinfunction "10_10") (pintype "passive"))
      (node (ref "JP2") (pin "8") (pinfunction "8_8") (pintype "passive"))
      (node (ref "RN1") (pin "8") (pinfunction "1_8") (pintype "passive"))
      (node (ref "RN2") (pin "2") (pinfunction "2_2") (pintype "passive"))
    )
    (net (code "111") (name "Net-(RN4B-1)") (class "Default")
      (node (ref "JP13") (pin "2") (pinfunction "2_2") (pintype "passive"))
      (node (ref "JP3") (pin "2") (pinfunction "2_2") (pintype "passive"))
      (node (ref "RN4") (pin "2") (pinfunction "1_2") (pintype "passive"))
      (node (ref "RN5") (pin "8") (pinfunction "8_8") (pintype "passive"))
    )
    (net (code "112") (name "Net-(RN4C-1)") (class "Default")
      (node (ref "JP13") (pin "3") (pinfunction "3_3") (pintype "passive"))
      (node (ref "JP3") (pin "3") (pinfunction "3_3") (pintype "passive"))
      (node (ref "RN4") (pin "3") (pinfunction "1_3") (pintype "passive"))
      (node (ref "RN5") (pin "7") (pinfunction "7_7") (pintype "passive"))
    )
    (net (code "113") (name "Net-(RN4D-1)") (class "Default")
      (node (ref "JP13") (pin "4") (pinfunction "4_4") (pintype "passive"))
      (node (ref "JP3") (pin "4") (pinfunction "4_4") (pintype "passive"))
      (node (ref "RN4") (pin "4") (pinfunction "1_4") (pintype "passive"))
      (node (ref "RN5") (pin "6") (pinfunction "6_6") (pintype "passive"))
    )
    (net (code "114") (name "Net-(RN4E-1)") (class "Default")
      (node (ref "JP13") (pin "7") (pinfunction "7_7") (pintype "passive"))
      (node (ref "JP3") (pin "5") (pinfunction "5_5") (pintype "passive"))
      (node (ref "RN4") (pin "5") (pinfunction "1_5") (pintype "passive"))
      (node (ref "RN5") (pin "5") (pinfunction "5_5") (pintype "passive"))
    )
    (net (code "115") (name "Net-(RN4F-1)") (class "Default")
      (node (ref "JP13") (pin "8") (pinfunction "8_8") (pintype "passive"))
      (node (ref "JP3") (pin "6") (pinfunction "6_6") (pintype "passive"))
      (node (ref "RN4") (pin "6") (pinfunction "1_6") (pintype "passive"))
      (node (ref "RN5") (pin "4") (pinfunction "4_4") (pintype "passive"))
    )
    (net (code "116") (name "Net-(RN4G-1)") (class "Default")
      (node (ref "JP13") (pin "9") (pinfunction "9_9") (pintype "passive"))
      (node (ref "JP3") (pin "7") (pinfunction "7_7") (pintype "passive"))
      (node (ref "RN4") (pin "7") (pinfunction "1_7") (pintype "passive"))
      (node (ref "RN5") (pin "3") (pinfunction "3_3") (pintype "passive"))
    )
    (net (code "117") (name "Net-(RN4H-1)") (class "Default")
      (node (ref "JP13") (pin "10") (pinfunction "10_10") (pintype "passive"))
      (node (ref "JP3") (pin "8") (pinfunction "8_8") (pintype "passive"))
      (node (ref "RN4") (pin "8") (pinfunction "1_8") (pintype "passive"))
      (node (ref "RN5") (pin "2") (pinfunction "2_2") (pintype "passive"))
    )
    (net (code "118") (name "unconnected-(H1-MOUNT-PadB3,3)") (class "Default")
      (node (ref "H1") (pin "B3,3") (pinfunction "MOUNT_B3,3") (pintype "passive"))
    )
    (net (code "119") (name "unconnected-(H2-MOUNT-PadB3,3)") (class "Default")
      (node (ref "H2") (pin "B3,3") (pinfunction "MOUNT_B3,3") (pintype "passive"))
    )
    (net (code "120") (name "unconnected-(H3-MOUNT-PadB3,3)") (class "Default")
      (node (ref "H3") (pin "B3,3") (pinfunction "MOUNT_B3,3") (pintype "passive"))
    )
    (net (code "121") (name "unconnected-(H4-MOUNT-PadB3,3)") (class "Default")
      (node (ref "H4") (pin "B3,3") (pinfunction "MOUNT_B3,3") (pintype "passive"))
    )
    (net (code "122") (name "unconnected-(IC3A-QH*-Pad9)") (class "Default")
      (node (ref "IC3") (pin "9") (pinfunction "QH*_9") (pintype "tri_state"))
    )
    (net (code "123") (name "unconnected-(IC5A-QH*-Pad9)") (class "Default")
      (node (ref "IC5") (pin "9") (pinfunction "QH*_9") (pintype "tri_state"))
    )
    (net (code "124") (name "unconnected-(IC6A-+IN-Pad3)") (class "Default")
      (node (ref "IC6") (pin "3") (pinfunction "+IN_3") (pintype "input"))
    )
    (net (code "125") (name "unconnected-(IC6B-+IN-Pad5)") (class "Default")
      (node (ref "IC6") (pin "5") (pinfunction "+IN_5") (pintype "input"))
    )
    (net (code "126") (name "unconnected-(IC6C-+IN-Pad10)") (class "Default")
      (node (ref "IC6") (pin "10") (pinfunction "+IN_10") (pintype "input"))
    )
    (net (code "127") (name "unconnected-(IC6D-+IN-Pad12)") (class "Default")
      (node (ref "IC6") (pin "12") (pinfunction "+IN_12") (pintype "input"))
    )
    (net (code "128") (name "unconnected-(IC7-RS-Pad8)") (class "Default")
      (node (ref "IC7") (pin "8") (pinfunction "RS_8") (pintype "input"))
    )
    (net (code "129") (name "unconnected-(IC7-VREF-Pad5)") (class "Default")
      (node (ref "IC7") (pin "5") (pinfunction "VREF_5") (pintype "output"))
    )
    (net (code "130") (name "unconnected-(IC9A-+IN-Pad3)") (class "Default")
      (node (ref "IC9") (pin "3") (pinfunction "+IN_3") (pintype "input"))
    )
    (net (code "131") (name "unconnected-(IC9B-+IN-Pad5)") (class "Default")
      (node (ref "IC9") (pin "5") (pinfunction "+IN_5") (pintype "input"))
    )
    (net (code "132") (name "unconnected-(IC9C-+IN-Pad10)") (class "Default")
      (node (ref "IC9") (pin "10") (pinfunction "+IN_10") (pintype "input"))
    )
    (net (code "133") (name "unconnected-(IC9D-+IN-Pad12)") (class "Default")
      (node (ref "IC9") (pin "12") (pinfunction "+IN_12") (pintype "input"))
    )
    (net (code "134") (name "unconnected-(J3-Pad2)") (class "Default")
      (node (ref "J3") (pin "2") (pinfunction "2_2") (pintype "passive"))
    )
    (net (code "135") (name "unconnected-(JP4-Pad1)") (class "Default")
      (node (ref "JP4") (pin "1") (pinfunction "1_1") (pintype "passive"))
    )
    (net (code "136") (name "unconnected-(JP4-Pad2)") (class "Default")
      (node (ref "JP4") (pin "2") (pinfunction "2_2") (pintype "passive"))
    )
    (net (code "137") (name "unconnected-(JP4-Pad3)") (class "Default")
      (node (ref "JP4") (pin "3") (pinfunction "3_3") (pintype "passive"))
    )
    (net (code "138") (name "unconnected-(JP4-Pad4)") (class "Default")
      (node (ref "JP4") (pin "4") (pinfunction "4_4") (pintype "passive"))
    )
    (net (code "139") (name "unconnected-(JP7-Pad1)") (class "Default")
      (node (ref "JP7") (pin "1") (pinfunction "1_1") (pintype "passive"))
    )
    (net (code "140") (name "unconnected-(JP7-Pad2)") (class "Default")
      (node (ref "JP7") (pin "2") (pinfunction "2_2") (pintype "passive"))
    )
    (net (code "141") (name "unconnected-(JP7-Pad3)") (class "Default")
      (node (ref "JP7") (pin "3") (pinfunction "3_3") (pintype "passive"))
    )
    (net (code "142") (name "unconnected-(JP7-Pad4)") (class "Default")
      (node (ref "JP7") (pin "4") (pinfunction "4_4") (pintype "passive"))
    )
    (net (code "143") (name "unconnected-(JP7-Pad5)") (class "Default")
      (node (ref "JP7") (pin "5") (pinfunction "5_5") (pintype "passive"))
    )
    (net (code "144") (name "unconnected-(JP7-Pad6)") (class "Default")
      (node (ref "JP7") (pin "6") (pinfunction "6_6") (pintype "passive"))
    )
    (net (code "145") (name "unconnected-(JP8-Pad1)") (class "Default")
      (node (ref "JP8") (pin "1") (pinfunction "1_1") (pintype "passive"))
    )
    (net (code "146") (name "unconnected-(JP8-Pad2)") (class "Default")
      (node (ref "JP8") (pin "2") (pinfunction "2_2") (pintype "passive"))
    )
    (net (code "147") (name "unconnected-(JP8-Pad3)") (class "Default")
      (node (ref "JP8") (pin "3") (pinfunction "3_3") (pintype "passive"))
    )
    (net (code "148") (name "unconnected-(JP8-Pad4)") (class "Default")
      (node (ref "JP8") (pin "4") (pinfunction "4_4") (pintype "passive"))
    )
    (net (code "149") (name "unconnected-(JP9-Pad1)") (class "Default")
      (node (ref "JP9") (pin "1") (pinfunction "1_1") (pintype "passive"))
    )
    (net (code "150") (name "unconnected-(JP9-Pad2)") (class "Default")
      (node (ref "JP9") (pin "2") (pinfunction "2_2") (pintype "passive"))
    )
    (net (code "151") (name "unconnected-(JP9-Pad3)") (class "Default")
      (node (ref "JP9") (pin "3") (pinfunction "3_3") (pintype "passive"))
    )
    (net (code "152") (name "unconnected-(JP9-Pad4)") (class "Default")
      (node (ref "JP9") (pin "4") (pinfunction "4_4") (pintype "passive"))
    )
    (net (code "153") (name "unconnected-(JP10-Pad1)") (class "Default")
      (node (ref "JP10") (pin "1") (pinfunction "1_1") (pintype "passive"))
    )
    (net (code "154") (name "unconnected-(JP10-Pad2)") (class "Default")
      (node (ref "JP10") (pin "2") (pinfunction "2_2") (pintype "passive"))
    )
    (net (code "155") (name "unconnected-(JP10-Pad3)") (class "Default")
      (node (ref "JP10") (pin "3") (pinfunction "3_3") (pintype "passive"))
    )
    (net (code "156") (name "unconnected-(JP10-Pad4)") (class "Default")
      (node (ref "JP10") (pin "4") (pinfunction "4_4") (pintype "passive"))
    )
    (net (code "157") (name "unconnected-(JP11-Pad1)") (class "Default")
      (node (ref "JP11") (pin "1") (pinfunction "1_1") (pintype "passive"))
    )
    (net (code "158") (name "unconnected-(JP11-Pad2)") (class "Default")
      (node (ref "JP11") (pin "2") (pinfunction "2_2") (pintype "passive"))
    )
    (net (code "159") (name "unconnected-(JP11-Pad3)") (class "Default")
      (node (ref "JP11") (pin "3") (pinfunction "3_3") (pintype "passive"))
    )
    (net (code "160") (name "unconnected-(JP11-Pad4)") (class "Default")
      (node (ref "JP11") (pin "4") (pinfunction "4_4") (pintype "passive"))
    )
    (net (code "161") (name "unconnected-(JP11-Pad5)") (class "Default")
      (node (ref "JP11") (pin "5") (pinfunction "5_5") (pintype "passive"))
    )
    (net (code "162") (name "unconnected-(JP11-Pad6)") (class "Default")
      (node (ref "JP11") (pin "6") (pinfunction "6_6") (pintype "passive"))
    )
    (net (code "163") (name "unconnected-(JP13-Pad5)") (class "Default")
      (node (ref "JP13") (pin "5") (pinfunction "5_5") (pintype "passive"))
    )
    (net (code "164") (name "unconnected-(JP13-Pad6)") (class "Default")
      (node (ref "JP13") (pin "6") (pinfunction "6_6") (pintype "passive"))
    )
    (net (code "165") (name "unconnected-(JP14-Pad5)") (class "Default")
      (node (ref "JP14") (pin "5") (pinfunction "5_5") (pintype "passive"))
    )
    (net (code "166") (name "unconnected-(JP14-Pad6)") (class "Default")
      (node (ref "JP14") (pin "6") (pinfunction "6_6") (pintype "passive"))
    )
    (net (code "167") (name "unconnected-(JP15-Pad5)") (class "Default")
      (node (ref "JP15") (pin "5") (pinfunction "5_5") (pintype "passive"))
    )
    (net (code "168") (name "unconnected-(JP15-Pad6)") (class "Default")
      (node (ref "JP15") (pin "6") (pinfunction "6_6") (pintype "passive"))
    )
    (net (code "169") (name "unconnected-(U$1-PadBOOT0)") (class "Default")
      (node (ref "U$1") (pin "BOOT0") (pinfunction "BOOT0_BOOT0") (pintype "bidirectional"))
    )
    (net (code "170") (name "unconnected-(U$1-PadIOREF2)") (class "Default")
      (node (ref "U$1") (pin "IOREF2") (pinfunction "IOREF2_IOREF2") (pintype "input"))
    )
    (net (code "171") (name "unconnected-(U$1-PadNC1-PF7)") (class "Default")
      (node (ref "U$1") (pin "NC1-PF7") (pinfunction "NC1-PF7_NC1-PF7") (pintype "bidirectional"))
    )
    (net (code "172") (name "unconnected-(U$1-PadNC2-PF6)") (class "Default")
      (node (ref "U$1") (pin "NC2-PF6") (pinfunction "NC2-PF6_NC2-PF6") (pintype "bidirectional"))
    )
    (net (code "173") (name "unconnected-(U$1-PadNC3)") (class "Default")
      (node (ref "U$1") (pin "NC3") (pinfunction "NC3_NC3") (pintype "no_connect"))
    )
    (net (code "174") (name "unconnected-(U$1-PadNC4)") (class "Default")
      (node (ref "U$1") (pin "NC4") (pinfunction "NC4_NC4") (pintype "no_connect"))
    )
    (net (code "175") (name "unconnected-(U$1-PadNC5-PD8)") (class "Default")
      (node (ref "U$1") (pin "NC5-PD8") (pinfunction "NC5-PD8_NC5-PD8") (pintype "bidirectional"))
    )
    (net (code "176") (name "unconnected-(U$1-PadNC6-PB11)") (class "Default")
      (node (ref "U$1") (pin "NC6-PB11") (pinfunction "NC6-PB11_NC6-PB11") (pintype "no_connect"))
    )
    (net (code "177") (name "unconnected-(U$1-PadNC7-PF5)") (class "Default")
      (node (ref "U$1") (pin "NC7-PF5") (pinfunction "NC7-PF5_NC7-PF5") (pintype "bidirectional"))
    )
    (net (code "178") (name "unconnected-(U$1-PadNC8-PF4)") (class "Default")
      (node (ref "U$1") (pin "NC8-PF4") (pinfunction "NC8-PF4_NC8-PF4") (pintype "bidirectional"))
    )
    (net (code "179") (name "unconnected-(U$1-PadNRESET)") (class "Default")
      (node (ref "U$1") (pin "NRESET") (pinfunction "NRESET_NRESET") (pintype "input"))
    )
    (net (code "180") (name "unconnected-(U$1-PadPA0)") (class "Default")
      (node (ref "U$1") (pin "PA0") (pinfunction "PA0_PA0") (pintype "bidirectional"))
    )
    (net (code "181") (name "unconnected-(U$1-PadPA1)") (class "Default")
      (node (ref "U$1") (pin "PA1") (pinfunction "PA1_PA1") (pintype "bidirectional"))
    )
    (net (code "182") (name "unconnected-(U$1-PadPA2)") (class "Default")
      (node (ref "U$1") (pin "PA2") (pinfunction "PA2_PA2") (pintype "bidirectional"))
    )
    (net (code "183") (name "unconnected-(U$1-PadPA3)") (class "Default")
      (node (ref "U$1") (pin "PA3") (pinfunction "PA3_PA3") (pintype "bidirectional"))
    )
    (net (code "184") (name "unconnected-(U$1-PadPA4)") (class "Default")
      (node (ref "U$1") (pin "PA4") (pinfunction "PA4_PA4") (pintype "bidirectional"))
    )
    (net (code "185") (name "unconnected-(U$1-PadPA5)") (class "Default")
      (node (ref "U$1") (pin "PA5") (pinfunction "PA5_PA5") (pintype "bidirectional"))
    )
    (net (code "186") (name "unconnected-(U$1-PadPA6)") (class "Default")
      (node (ref "U$1") (pin "PA6") (pinfunction "PA6_PA6") (pintype "bidirectional"))
    )
    (net (code "187") (name "unconnected-(U$1-PadPA7)") (class "Default")
      (node (ref "U$1") (pin "PA7") (pinfunction "PA7_PA7") (pintype "bidirectional"))
    )
    (net (code "188") (name "unconnected-(U$1-PadPA8)") (class "Default")
      (node (ref "U$1") (pin "PA8") (pinfunction "PA8_PA8") (pintype "bidirectional"))
    )
    (net (code "189") (name "unconnected-(U$1-PadPA9)") (class "Default")
      (node (ref "U$1") (pin "PA9") (pinfunction "PA9_PA9") (pintype "bidirectional"))
    )
    (net (code "190") (name "unconnected-(U$1-PadPA10)") (class "Default")
      (node (ref "U$1") (pin "PA10") (pinfunction "PA10_PA10") (pintype "bidirectional"))
    )
    (net (code "191") (name "unconnected-(U$1-PadPA11)") (class "Default")
      (node (ref "U$1") (pin "PA11") (pinfunction "PA11_PA11") (pintype "bidirectional"))
    )
    (net (code "192") (name "unconnected-(U$1-PadPA12)") (class "Default")
      (node (ref "U$1") (pin "PA12") (pinfunction "PA12_PA12") (pintype "bidirectional"))
    )
    (net (code "193") (name "unconnected-(U$1-PadPA13)") (class "Default")
      (node (ref "U$1") (pin "PA13") (pinfunction "PA13_PA13") (pintype "bidirectional"))
    )
    (net (code "194") (name "unconnected-(U$1-PadPA14)") (class "Default")
      (node (ref "U$1") (pin "PA14") (pinfunction "PA14_PA14") (pintype "bidirectional"))
    )
    (net (code "195") (name "unconnected-(U$1-PadPA15)") (class "Default")
      (node (ref "U$1") (pin "PA15") (pinfunction "PA15_PA15") (pintype "bidirectional"))
    )
    (net (code "196") (name "unconnected-(U$1-PadPB0)") (class "Default")
      (node (ref "U$1") (pin "PB0") (pinfunction "PB0_PB0") (pintype "bidirectional"))
    )
    (net (code "197") (name "unconnected-(U$1-PadPB1)") (class "Default")
      (node (ref "U$1") (pin "PB1") (pinfunction "PB1_PB1") (pintype "bidirectional"))
    )
    (net (code "198") (name "unconnected-(U$1-PadPB2)") (class "Default")
      (node (ref "U$1") (pin "PB2") (pinfunction "PB2_PB2") (pintype "bidirectional"))
    )
    (net (code "199") (name "unconnected-(U$1-PadPB3)") (class "Default")
      (node (ref "U$1") (pin "PB3") (pinfunction "PB3_PB3") (pintype "bidirectional"))
    )
    (net (code "200") (name "unconnected-(U$1-PadPB4)") (class "Default")
      (node (ref "U$1") (pin "PB4") (pinfunction "PB4_PB4") (pintype "bidirectional"))
    )
    (net (code "201") (name "unconnected-(U$1-PadPB5)") (class "Default")
      (node (ref "U$1") (pin "PB5") (pinfunction "PB5_PB5") (pintype "bidirectional"))
    )
    (net (code "202") (name "unconnected-(U$1-PadPB6)") (class "Default")
      (node (ref "U$1") (pin "PB6") (pinfunction "PB6_PB6") (pintype "bidirectional"))
    )
    (net (code "203") (name "unconnected-(U$1-PadPB7)") (class "Default")
      (node (ref "U$1") (pin "PB7") (pinfunction "PB7_PB7") (pintype "bidirectional"))
    )
    (net (code "204") (name "unconnected-(U$1-PadPB10)") (class "Default")
      (node (ref "U$1") (pin "PB10") (pinfunction "PB10_PB10") (pintype "bidirectional"))
    )
    (net (code "205") (name "unconnected-(U$1-PadPB12)") (class "Default")
      (node (ref "U$1") (pin "PB12") (pinfunction "PB12_PB12") (pintype "bidirectional"))
    )
    (net (code "206") (name "unconnected-(U$1-PadPB13)") (class "Default")
      (node (ref "U$1") (pin "PB13") (pinfunction "PB13_PB13") (pintype "bidirectional"))
    )
    (net (code "207") (name "unconnected-(U$1-PadPB14)") (class "Default")
      (node (ref "U$1") (pin "PB14") (pinfunction "PB14_PB14") (pintype "bidirectional"))
    )
    (net (code "208") (name "unconnected-(U$1-PadPB15)") (class "Default")
      (node (ref "U$1") (pin "PB15") (pinfunction "PB15_PB15") (pintype "bidirectional"))
    )
    (net (code "209") (name "unconnected-(U$1-PadPC0)") (class "Default")
      (node (ref "U$1") (pin "PC0") (pinfunction "PC0_PC0") (pintype "bidirectional"))
    )
    (net (code "210") (name "unconnected-(U$1-PadPC1)") (class "Default")
      (node (ref "U$1") (pin "PC1") (pinfunction "PC1_PC1") (pintype "bidirectional"))
    )
    (net (code "211") (name "unconnected-(U$1-PadPC2)") (class "Default")
      (node (ref "U$1") (pin "PC2") (pinfunction "PC2_PC2") (pintype "bidirectional"))
    )
    (net (code "212") (name "unconnected-(U$1-PadPC3)") (class "Default")
      (node (ref "U$1") (pin "PC3") (pinfunction "PC3_PC3") (pintype "bidirectional"))
    )
    (net (code "213") (name "unconnected-(U$1-PadPC4)") (class "Default")
      (node (ref "U$1") (pin "PC4") (pinfunction "PC4_PC4") (pintype "bidirectional"))
    )
    (net (code "214") (name "unconnected-(U$1-PadPC5)") (class "Default")
      (node (ref "U$1") (pin "PC5") (pinfunction "PC5_PC5") (pintype "bidirectional"))
    )
    (net (code "215") (name "unconnected-(U$1-PadPC6)") (class "Default")
      (node (ref "U$1") (pin "PC6") (pinfunction "PC6_PC6") (pintype "bidirectional"))
    )
    (net (code "216") (name "unconnected-(U$1-PadPC7)") (class "Default")
      (node (ref "U$1") (pin "PC7") (pinfunction "PC7_PC7") (pintype "bidirectional"))
    )
    (net (code "217") (name "unconnected-(U$1-PadPC8)") (class "Default")
      (node (ref "U$1") (pin "PC8") (pinfunction "PC8_PC8") (pintype "bidirectional"))
    )
    (net (code "218") (name "unconnected-(U$1-PadPC9)") (class "Default")
      (node (ref "U$1") (pin "PC9") (pinfunction "PC9_PC9") (pintype "bidirectional"))
    )
    (net (code "219") (name "unconnected-(U$1-PadPC10)") (class "Default")
      (node (ref "U$1") (pin "PC10") (pinfunction "PC10_PC10") (pintype "bidirectional"))
    )
    (net (code "220") (name "unconnected-(U$1-PadPC11)") (class "Default")
      (node (ref "U$1") (pin "PC11") (pinfunction "PC11_PC11") (pintype "bidirectional"))
    )
    (net (code "221") (name "unconnected-(U$1-PadPC12)") (class "Default")
      (node (ref "U$1") (pin "PC12") (pinfunction "PC12_PC12") (pintype "bidirectional"))
    )
    (net (code "222") (name "unconnected-(U$1-PadPC13)") (class "Default")
      (node (ref "U$1") (pin "PC13") (pinfunction "PC13_PC13") (pintype "bidirectional"))
    )
    (net (code "223") (name "unconnected-(U$1-PadPC14)") (class "Default")
      (node (ref "U$1") (pin "PC14") (pinfunction "PC14_PC14") (pintype "bidirectional"))
    )
    (net (code "224") (name "unconnected-(U$1-PadPC15)") (class "Default")
      (node (ref "U$1") (pin "PC15") (pinfunction "PC15_PC15") (pintype "bidirectional"))
    )
    (net (code "225") (name "unconnected-(U$1-PadPD2)") (class "Default")
      (node (ref "U$1") (pin "PD2") (pinfunction "PD2_PD2") (pintype "bidirectional"))
    )
    (net (code "226") (name "unconnected-(U$1-PadPF0-PH0)") (class "Default")
      (node (ref "U$1") (pin "PF0-PH0") (pinfunction "PF0-PH0_PF0-PH0") (pintype "bidirectional"))
    )
    (net (code "227") (name "unconnected-(U$1-PadPF1-PH1)") (class "Default")
      (node (ref "U$1") (pin "PF1-PH1") (pinfunction "PF1-PH1_PF1-PH1") (pintype "bidirectional"))
    )
  )
)
